# Sheet2.net
KiCad netlist of a schematic drawn in Altium Designer
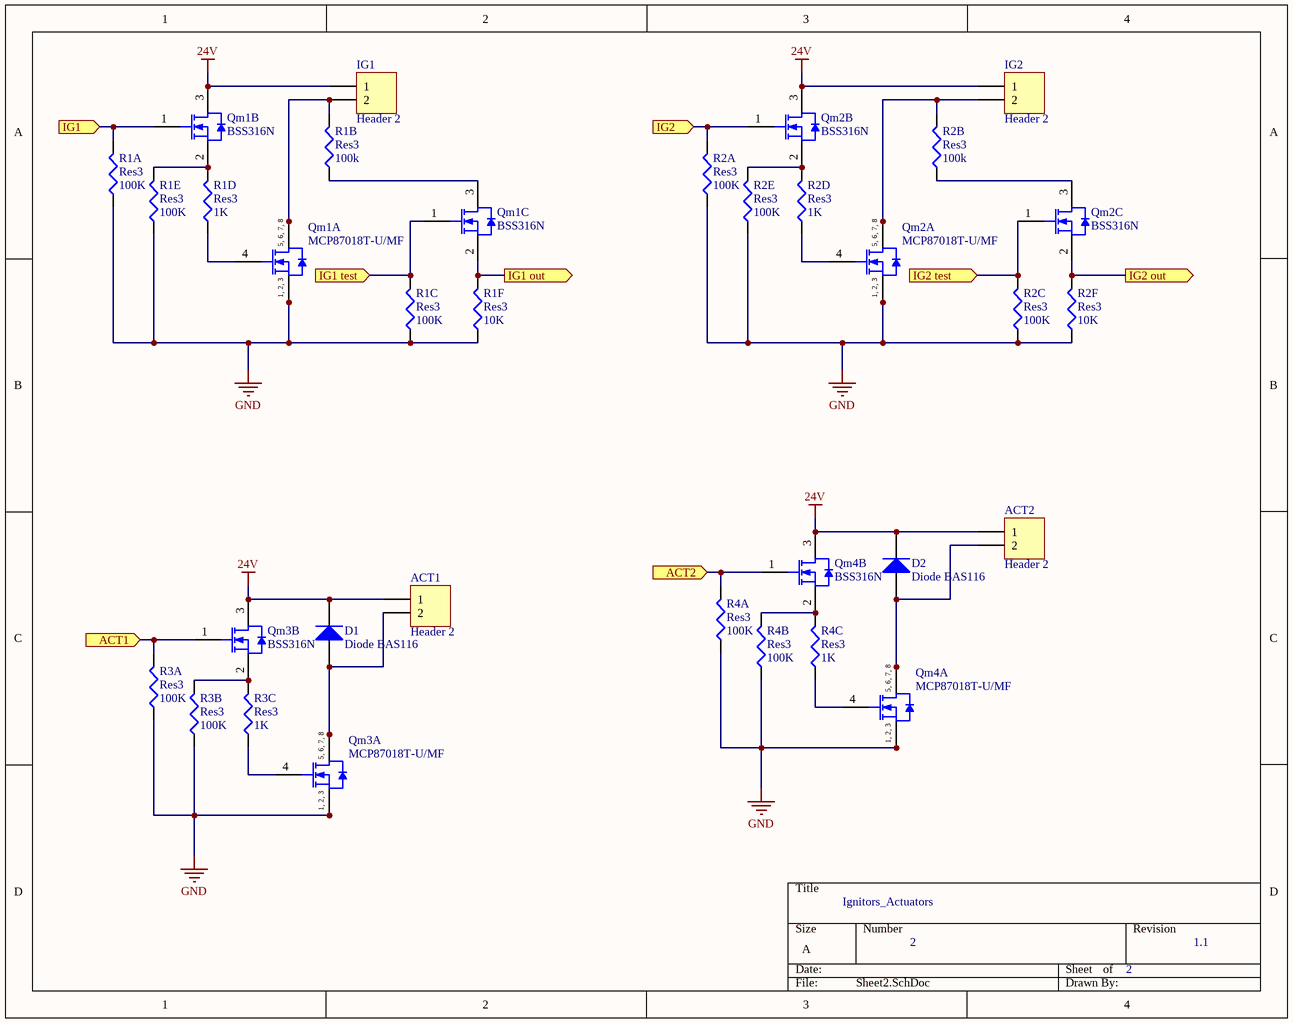
[diagram p0: Sheet2.SchDoc]

(export (version "E")
  (design (tool "Eeschema 10.0.6"))
  (components
    (comp (ref "ACT1")
      (value "Header 2")
      (footprint "HDR1X2")
      (description "Header, 2-Pin")
      (fields (field (name "PUBLISHER") "Altium Limited"))
      (libsource (lib "Miscellaneous Connectors") (part "Header 2"))
    )
    (comp (ref "ACT2")
      (value "Header 2")
      (footprint "HDR1X2")
      (description "Header, 2-Pin")
      (fields (field (name "PUBLISHER") "Altium Limited"))
      (libsource (lib "Miscellaneous Connectors") (part "Header 2"))
    )
    (comp (ref "D1")
      (value "Diode BAS116")
      (footprint "SOT-23_N")
      (description "Silicon Low Leakage Diode")
      (fields (field (name "PUBLISHER") "Altium Limited"))
      (libsource (lib "Miscellaneous Devices") (part "Diode BAS116"))
    )
    (comp (ref "D2")
      (value "Diode BAS116")
      (footprint "SOT-23_N")
      (description "Silicon Low Leakage Diode")
      (fields (field (name "PUBLISHER") "Altium Limited"))
      (libsource (lib "Miscellaneous Devices") (part "Diode BAS116"))
    )
    (comp (ref "IG1")
      (value "Header 2")
      (footprint "HDR1X2")
      (description "Header, 2-Pin")
      (fields (field (name "PUBLISHER") "Altium Limited"))
      (libsource (lib "Miscellaneous Connectors") (part "Header 2"))
    )
    (comp (ref "IG2")
      (value "Header 2")
      (footprint "HDR1X2")
      (description "Header, 2-Pin")
      (fields (field (name "PUBLISHER") "Altium Limited"))
      (libsource (lib "Miscellaneous Connectors") (part "Header 2"))
    )
    (comp (ref "Qm1A")
      (value "MCP87018T-U/MF")
      (footprint "MCHP-PDFN-MF8_V")
      (fields (field (name "MANUFACTURER") "Microchip"))
      (libsource (lib "Microchip Power Management Power MOSFET") (part "MCP87018T-U/MF"))
    )
    (comp (ref "Qm1B")
      (value "BSS316N")
      (footprint "INF-PG-SOT23_N")
      (fields (field (name "MANUFACTURER") "Infineon"))
      (libsource (lib "Infineon_Power_MOSFET") (part "BSS316N"))
    )
    (comp (ref "Qm1C")
      (value "BSS316N")
      (footprint "INF-PG-SOT23_N")
      (fields (field (name "MANUFACTURER") "Infineon"))
      (libsource (lib "Infineon_Power_MOSFET") (part "BSS316N"))
    )
    (comp (ref "Qm2A")
      (value "MCP87018T-U/MF")
      (footprint "MCHP-PDFN-MF8_V")
      (fields (field (name "MANUFACTURER") "Microchip"))
      (libsource (lib "Microchip Power Management Power MOSFET") (part "MCP87018T-U/MF"))
    )
    (comp (ref "Qm2B")
      (value "BSS316N")
      (footprint "INF-PG-SOT23_N")
      (fields (field (name "MANUFACTURER") "Infineon"))
      (libsource (lib "Infineon_Power_MOSFET") (part "BSS316N"))
    )
    (comp (ref "Qm2C")
      (value "BSS316N")
      (footprint "INF-PG-SOT23_N")
      (fields (field (name "MANUFACTURER") "Infineon"))
      (libsource (lib "Infineon_Power_MOSFET") (part "BSS316N"))
    )
    (comp (ref "Qm3A")
      (value "MCP87018T-U/MF")
      (footprint "MCHP-PDFN-MF8_V")
      (fields (field (name "MANUFACTURER") "Microchip"))
      (libsource (lib "Microchip Power Management Power MOSFET") (part "MCP87018T-U/MF"))
    )
    (comp (ref "Qm3B")
      (value "BSS316N")
      (footprint "INF-PG-SOT23_N")
      (fields (field (name "MANUFACTURER") "Infineon"))
      (libsource (lib "Infineon_Power_MOSFET") (part "BSS316N"))
    )
    (comp (ref "Qm4A")
      (value "MCP87018T-U/MF")
      (footprint "MCHP-PDFN-MF8_V")
      (fields (field (name "MANUFACTURER") "Microchip"))
      (libsource (lib "Microchip Power Management Power MOSFET") (part "MCP87018T-U/MF"))
    )
    (comp (ref "Qm4B")
      (value "BSS316N")
      (footprint "INF-PG-SOT23_N")
      (fields (field (name "MANUFACTURER") "Infineon"))
      (libsource (lib "Infineon_Power_MOSFET") (part "BSS316N"))
    )
    (comp (ref "R1A")
      (value "Res3")
      (footprint "J1-0603")
      (description "Resistor")
      (fields (field (name "ALTIUM_VALUE") "100K") (field (name "PUBLISHER") "Altium Limited"))
      (libsource (lib "Miscellaneous Devices") (part "Res3"))
    )
    (comp (ref "R1B")
      (value "Res3")
      (footprint "J1-0603")
      (description "Resistor")
      (fields (field (name "ALTIUM_VALUE") "100k") (field (name "PUBLISHER") "Altium Limited"))
      (libsource (lib "Miscellaneous Devices") (part "Res3"))
    )
    (comp (ref "R1C")
      (value "Res3")
      (footprint "J1-0603")
      (description "Resistor")
      (fields (field (name "ALTIUM_VALUE") "100K") (field (name "PUBLISHER") "Altium Limited"))
      (libsource (lib "Miscellaneous Devices") (part "Res3"))
    )
    (comp (ref "R1D")
      (value "Res3")
      (footprint "J1-0603")
      (description "Resistor")
      (fields (field (name "ALTIUM_VALUE") "1K") (field (name "PUBLISHER") "Altium Limited"))
      (libsource (lib "Miscellaneous Devices") (part "Res3"))
    )
    (comp (ref "R1E")
      (value "Res3")
      (footprint "J1-0603")
      (description "Resistor")
      (fields (field (name "ALTIUM_VALUE") "100K") (field (name "PUBLISHER") "Altium Limited"))
      (libsource (lib "Miscellaneous Devices") (part "Res3"))
    )
    (comp (ref "R1F")
      (value "Res3")
      (footprint "J1-0603")
      (description "Resistor")
      (fields (field (name "ALTIUM_VALUE") "10K") (field (name "PUBLISHER") "Altium Limited"))
      (libsource (lib "Miscellaneous Devices") (part "Res3"))
    )
    (comp (ref "R2A")
      (value "Res3")
      (footprint "J1-0603")
      (description "Resistor")
      (fields (field (name "ALTIUM_VALUE") "100K") (field (name "PUBLISHER") "Altium Limited"))
      (libsource (lib "Miscellaneous Devices") (part "Res3"))
    )
    (comp (ref "R2B")
      (value "Res3")
      (footprint "J1-0603")
      (description "Resistor")
      (fields (field (name "ALTIUM_VALUE") "100k") (field (name "PUBLISHER") "Altium Limited"))
      (libsource (lib "Miscellaneous Devices") (part "Res3"))
    )
    (comp (ref "R2C")
      (value "Res3")
      (footprint "J1-0603")
      (description "Resistor")
      (fields (field (name "ALTIUM_VALUE") "100K") (field (name "PUBLISHER") "Altium Limited"))
      (libsource (lib "Miscellaneous Devices") (part "Res3"))
    )
    (comp (ref "R2D")
      (value "Res3")
      (footprint "J1-0603")
      (description "Resistor")
      (fields (field (name "ALTIUM_VALUE") "1K") (field (name "PUBLISHER") "Altium Limited"))
      (libsource (lib "Miscellaneous Devices") (part "Res3"))
    )
    (comp (ref "R2E")
      (value "Res3")
      (footprint "J1-0603")
      (description "Resistor")
      (fields (field (name "ALTIUM_VALUE") "100K") (field (name "PUBLISHER") "Altium Limited"))
      (libsource (lib "Miscellaneous Devices") (part "Res3"))
    )
    (comp (ref "R2F")
      (value "Res3")
      (footprint "J1-0603")
      (description "Resistor")
      (fields (field (name "ALTIUM_VALUE") "10K") (field (name "PUBLISHER") "Altium Limited"))
      (libsource (lib "Miscellaneous Devices") (part "Res3"))
    )
    (comp (ref "R3A")
      (value "Res3")
      (footprint "J1-0603")
      (description "Resistor")
      (fields (field (name "ALTIUM_VALUE") "100K") (field (name "PUBLISHER") "Altium Limited"))
      (libsource (lib "Miscellaneous Devices") (part "Res3"))
    )
    (comp (ref "R3B")
      (value "Res3")
      (footprint "J1-0603")
      (description "Resistor")
      (fields (field (name "ALTIUM_VALUE") "100K") (field (name "PUBLISHER") "Altium Limited"))
      (libsource (lib "Miscellaneous Devices") (part "Res3"))
    )
    (comp (ref "R3C")
      (value "Res3")
      (footprint "J1-0603")
      (description "Resistor")
      (fields (field (name "ALTIUM_VALUE") "1K") (field (name "PUBLISHER") "Altium Limited"))
      (libsource (lib "Miscellaneous Devices") (part "Res3"))
    )
    (comp (ref "R4A")
      (value "Res3")
      (footprint "J1-0603")
      (description "Resistor")
      (fields (field (name "ALTIUM_VALUE") "100K") (field (name "PUBLISHER") "Altium Limited"))
      (libsource (lib "Miscellaneous Devices") (part "Res3"))
    )
    (comp (ref "R4B")
      (value "Res3")
      (footprint "J1-0603")
      (description "Resistor")
      (fields (field (name "ALTIUM_VALUE") "100K") (field (name "PUBLISHER") "Altium Limited"))
      (libsource (lib "Miscellaneous Devices") (part "Res3"))
    )
    (comp (ref "R4C")
      (value "Res3")
      (footprint "J1-0603")
      (description "Resistor")
      (fields (field (name "ALTIUM_VALUE") "1K") (field (name "PUBLISHER") "Altium Limited"))
      (libsource (lib "Miscellaneous Devices") (part "Res3"))
    )
  )
  (nets
    (net (code "1") (name "/ACT1") (class "Default")
      (node (ref "Qm3B") (pin "1") (pinfunction "GATE_1") (pintype "passive"))
      (node (ref "R3A") (pin "2") (pinfunction "2_2") (pintype "passive"))
    )
    (net (code "2") (name "/ACT2") (class "Default")
      (node (ref "Qm4B") (pin "1") (pinfunction "GATE_1") (pintype "passive"))
      (node (ref "R4A") (pin "2") (pinfunction "2_2") (pintype "passive"))
    )
    (net (code "3") (name "/IG1") (class "Default")
      (node (ref "Qm1B") (pin "1") (pinfunction "GATE_1") (pintype "passive"))
      (node (ref "R1A") (pin "2") (pinfunction "2_2") (pintype "passive"))
    )
    (net (code "4") (name "/IG1 out") (class "Default")
      (node (ref "Qm1C") (pin "2") (pinfunction "SOURCE_2") (pintype "passive"))
      (node (ref "R1F") (pin "2") (pinfunction "2_2") (pintype "passive"))
    )
    (net (code "5") (name "/IG1 test") (class "Default")
      (node (ref "Qm1C") (pin "1") (pinfunction "GATE_1") (pintype "passive"))
      (node (ref "R1C") (pin "2") (pinfunction "2_2") (pintype "passive"))
    )
    (net (code "6") (name "/IG2") (class "Default")
      (node (ref "Qm2B") (pin "1") (pinfunction "GATE_1") (pintype "passive"))
      (node (ref "R2A") (pin "2") (pinfunction "2_2") (pintype "passive"))
    )
    (net (code "7") (name "/IG2 out") (class "Default")
      (node (ref "Qm2C") (pin "2") (pinfunction "SOURCE_2") (pintype "passive"))
      (node (ref "R2F") (pin "2") (pinfunction "2_2") (pintype "passive"))
    )
    (net (code "8") (name "/IG2 test") (class "Default")
      (node (ref "Qm2C") (pin "1") (pinfunction "GATE_1") (pintype "passive"))
      (node (ref "R2C") (pin "2") (pinfunction "2_2") (pintype "passive"))
    )
    (net (code "9") (name "24V") (class "Default")
      (node (ref "ACT1") (pin "1") (pinfunction "1_1") (pintype "passive"))
      (node (ref "ACT2") (pin "1") (pinfunction "1_1") (pintype "passive"))
      (node (ref "D1") (pin "3") (pinfunction "K_3") (pintype "passive"))
      (node (ref "D2") (pin "3") (pinfunction "K_3") (pintype "passive"))
      (node (ref "IG1") (pin "1") (pinfunction "1_1") (pintype "passive"))
      (node (ref "IG2") (pin "1") (pinfunction "1_1") (pintype "passive"))
      (node (ref "Qm1B") (pin "3") (pinfunction "DRAIN_3") (pintype "passive"))
      (node (ref "Qm2B") (pin "3") (pinfunction "DRAIN_3") (pintype "passive"))
      (node (ref "Qm3B") (pin "3") (pinfunction "DRAIN_3") (pintype "passive"))
      (node (ref "Qm4B") (pin "3") (pinfunction "DRAIN_3") (pintype "passive"))
    )
    (net (code "10") (name "GND") (class "Default")
      (node (ref "Qm1A") (pin "1") (pinfunction "S_1") (pintype "passive"))
      (node (ref "Qm1A") (pin "2") (pinfunction "S_2") (pintype "passive"))
      (node (ref "Qm1A") (pin "3") (pinfunction "S_3") (pintype "passive"))
      (node (ref "Qm2A") (pin "1") (pinfunction "S_1") (pintype "passive"))
      (node (ref "Qm2A") (pin "2") (pinfunction "S_2") (pintype "passive"))
      (node (ref "Qm2A") (pin "3") (pinfunction "S_3") (pintype "passive"))
      (node (ref "Qm3A") (pin "1") (pinfunction "S_1") (pintype "passive"))
      (node (ref "Qm3A") (pin "2") (pinfunction "S_2") (pintype "passive"))
      (node (ref "Qm3A") (pin "3") (pinfunction "S_3") (pintype "passive"))
      (node (ref "Qm4A") (pin "1") (pinfunction "S_1") (pintype "passive"))
      (node (ref "Qm4A") (pin "2") (pinfunction "S_2") (pintype "passive"))
      (node (ref "Qm4A") (pin "3") (pinfunction "S_3") (pintype "passive"))
      (node (ref "R1A") (pin "1") (pinfunction "1_1") (pintype "passive"))
      (node (ref "R1C") (pin "1") (pinfunction "1_1") (pintype "passive"))
      (node (ref "R1E") (pin "1") (pinfunction "1_1") (pintype "passive"))
      (node (ref "R1F") (pin "1") (pinfunction "1_1") (pintype "passive"))
      (node (ref "R2A") (pin "1") (pinfunction "1_1") (pintype "passive"))
      (node (ref "R2C") (pin "1") (pinfunction "1_1") (pintype "passive"))
      (node (ref "R2E") (pin "1") (pinfunction "1_1") (pintype "passive"))
      (node (ref "R2F") (pin "1") (pinfunction "1_1") (pintype "passive"))
      (node (ref "R3A") (pin "1") (pinfunction "1_1") (pintype "passive"))
      (node (ref "R3B") (pin "1") (pinfunction "1_1") (pintype "passive"))
      (node (ref "R4A") (pin "1") (pinfunction "1_1") (pintype "passive"))
      (node (ref "R4B") (pin "1") (pinfunction "1_1") (pintype "passive"))
    )
    (net (code "11") (name "Net-(D1-A)") (class "Default")
      (node (ref "ACT1") (pin "2") (pinfunction "2_2") (pintype "passive"))
      (node (ref "D1") (pin "1") (pinfunction "A_1") (pintype "passive"))
      (node (ref "Qm3A") (pin "5") (pinfunction "D_5") (pintype "passive"))
      (node (ref "Qm3A") (pin "6") (pinfunction "D_6") (pintype "passive"))
      (node (ref "Qm3A") (pin "7") (pinfunction "D_7") (pintype "passive"))
      (node (ref "Qm3A") (pin "8") (pinfunction "D_8") (pintype "passive"))
    )
    (net (code "12") (name "Net-(D2-A)") (class "Default")
      (node (ref "ACT2") (pin "2") (pinfunction "2_2") (pintype "passive"))
      (node (ref "D2") (pin "1") (pinfunction "A_1") (pintype "passive"))
      (node (ref "Qm4A") (pin "5") (pinfunction "D_5") (pintype "passive"))
      (node (ref "Qm4A") (pin "6") (pinfunction "D_6") (pintype "passive"))
      (node (ref "Qm4A") (pin "7") (pinfunction "D_7") (pintype "passive"))
      (node (ref "Qm4A") (pin "8") (pinfunction "D_8") (pintype "passive"))
    )
    (net (code "13") (name "Net-(IG1-Pad2)") (class "Default")
      (node (ref "IG1") (pin "2") (pinfunction "2_2") (pintype "passive"))
      (node (ref "Qm1A") (pin "5") (pinfunction "D_5") (pintype "passive"))
      (node (ref "Qm1A") (pin "6") (pinfunction "D_6") (pintype "passive"))
      (node (ref "Qm1A") (pin "7") (pinfunction "D_7") (pintype "passive"))
      (node (ref "Qm1A") (pin "8") (pinfunction "D_8") (pintype "passive"))
      (node (ref "R1B") (pin "2") (pinfunction "2_2") (pintype "passive"))
    )
    (net (code "14") (name "Net-(IG2-Pad2)") (class "Default")
      (node (ref "IG2") (pin "2") (pinfunction "2_2") (pintype "passive"))
      (node (ref "Qm2A") (pin "5") (pinfunction "D_5") (pintype "passive"))
      (node (ref "Qm2A") (pin "6") (pinfunction "D_6") (pintype "passive"))
      (node (ref "Qm2A") (pin "7") (pinfunction "D_7") (pintype "passive"))
      (node (ref "Qm2A") (pin "8") (pinfunction "D_8") (pintype "passive"))
      (node (ref "R2B") (pin "2") (pinfunction "2_2") (pintype "passive"))
    )
    (net (code "15") (name "Net-(Qm1A-G)") (class "Default")
      (node (ref "Qm1A") (pin "4") (pinfunction "G_4") (pintype "passive"))
      (node (ref "R1D") (pin "1") (pinfunction "1_1") (pintype "passive"))
    )
    (net (code "16") (name "Net-(Qm1B-SOURCE)") (class "Default")
      (node (ref "Qm1B") (pin "2") (pinfunction "SOURCE_2") (pintype "passive"))
      (node (ref "R1D") (pin "2") (pinfunction "2_2") (pintype "passive"))
      (node (ref "R1E") (pin "2") (pinfunction "2_2") (pintype "passive"))
    )
    (net (code "17") (name "Net-(Qm1C-DRAIN)") (class "Default")
      (node (ref "Qm1C") (pin "3") (pinfunction "DRAIN_3") (pintype "passive"))
      (node (ref "R1B") (pin "1") (pinfunction "1_1") (pintype "passive"))
    )
    (net (code "18") (name "Net-(Qm2A-G)") (class "Default")
      (node (ref "Qm2A") (pin "4") (pinfunction "G_4") (pintype "passive"))
      (node (ref "R2D") (pin "1") (pinfunction "1_1") (pintype "passive"))
    )
    (net (code "19") (name "Net-(Qm2B-SOURCE)") (class "Default")
      (node (ref "Qm2B") (pin "2") (pinfunction "SOURCE_2") (pintype "passive"))
      (node (ref "R2D") (pin "2") (pinfunction "2_2") (pintype "passive"))
      (node (ref "R2E") (pin "2") (pinfunction "2_2") (pintype "passive"))
    )
    (net (code "20") (name "Net-(Qm2C-DRAIN)") (class "Default")
      (node (ref "Qm2C") (pin "3") (pinfunction "DRAIN_3") (pintype "passive"))
      (node (ref "R2B") (pin "1") (pinfunction "1_1") (pintype "passive"))
    )
    (net (code "21") (name "Net-(Qm3A-G)") (class "Default")
      (node (ref "Qm3A") (pin "4") (pinfunction "G_4") (pintype "passive"))
      (node (ref "R3C") (pin "1") (pinfunction "1_1") (pintype "passive"))
    )
    (net (code "22") (name "Net-(Qm3B-SOURCE)") (class "Default")
      (node (ref "Qm3B") (pin "2") (pinfunction "SOURCE_2") (pintype "passive"))
      (node (ref "R3B") (pin "2") (pinfunction "2_2") (pintype "passive"))
      (node (ref "R3C") (pin "2") (pinfunction "2_2") (pintype "passive"))
    )
    (net (code "23") (name "Net-(Qm4A-G)") (class "Default")
      (node (ref "Qm4A") (pin "4") (pinfunction "G_4") (pintype "passive"))
      (node (ref "R4C") (pin "1") (pinfunction "1_1") (pintype "passive"))
    )
    (net (code "24") (name "Net-(Qm4B-SOURCE)") (class "Default")
      (node (ref "Qm4B") (pin "2") (pinfunction "SOURCE_2") (pintype "passive"))
      (node (ref "R4B") (pin "2") (pinfunction "2_2") (pintype "passive"))
      (node (ref "R4C") (pin "2") (pinfunction "2_2") (pintype "passive"))
    )
  )
)
